# Nanocopter_V2_1.net
KiCad netlist of a schematic drawn in EAGLE
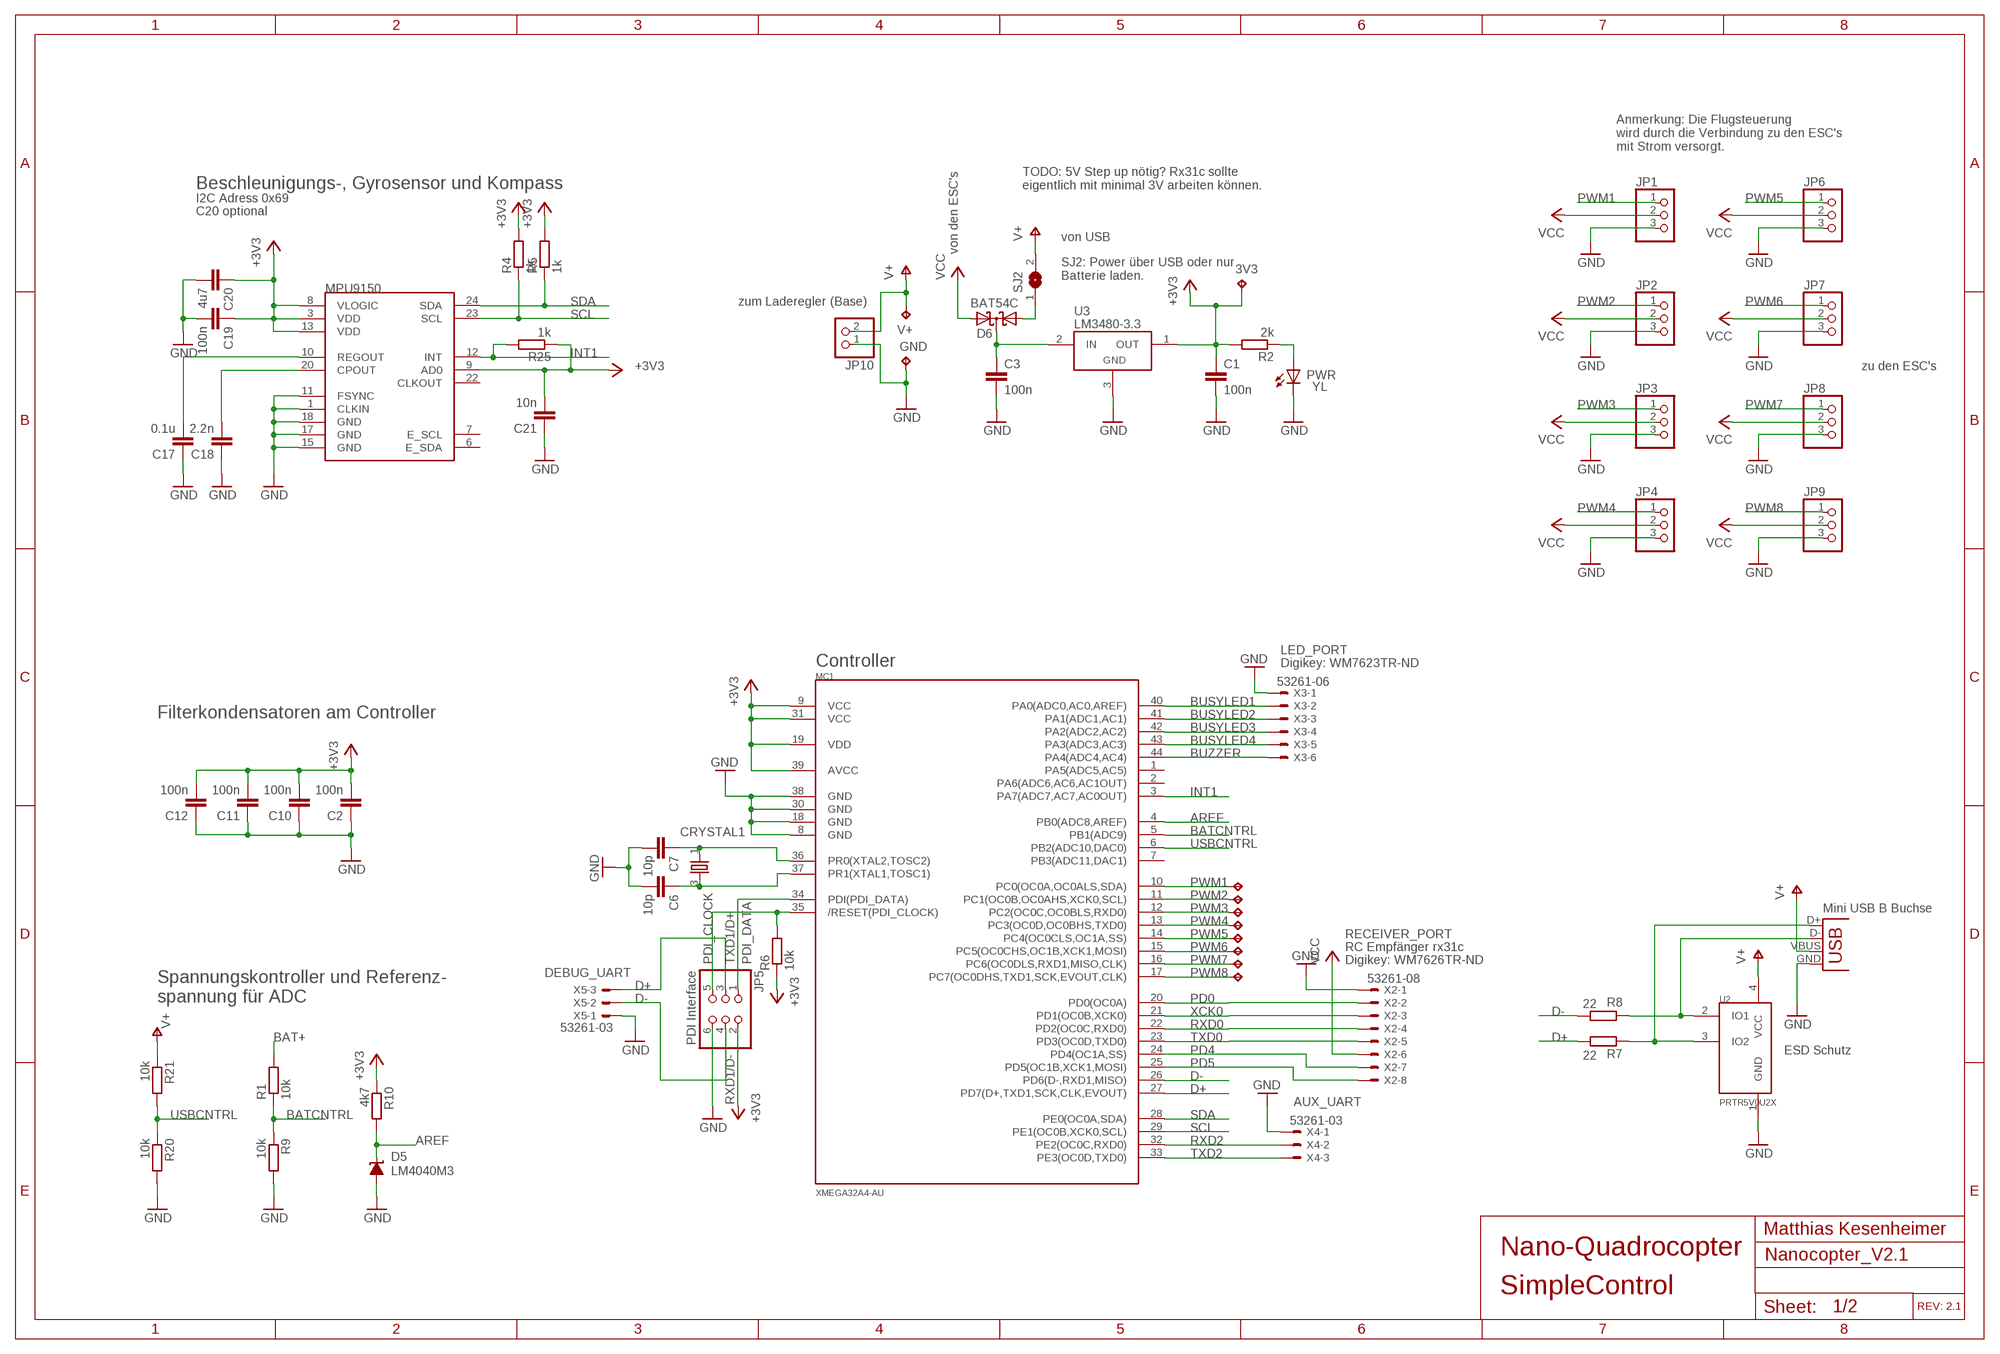
[diagram p0: schematic, sheet 1]
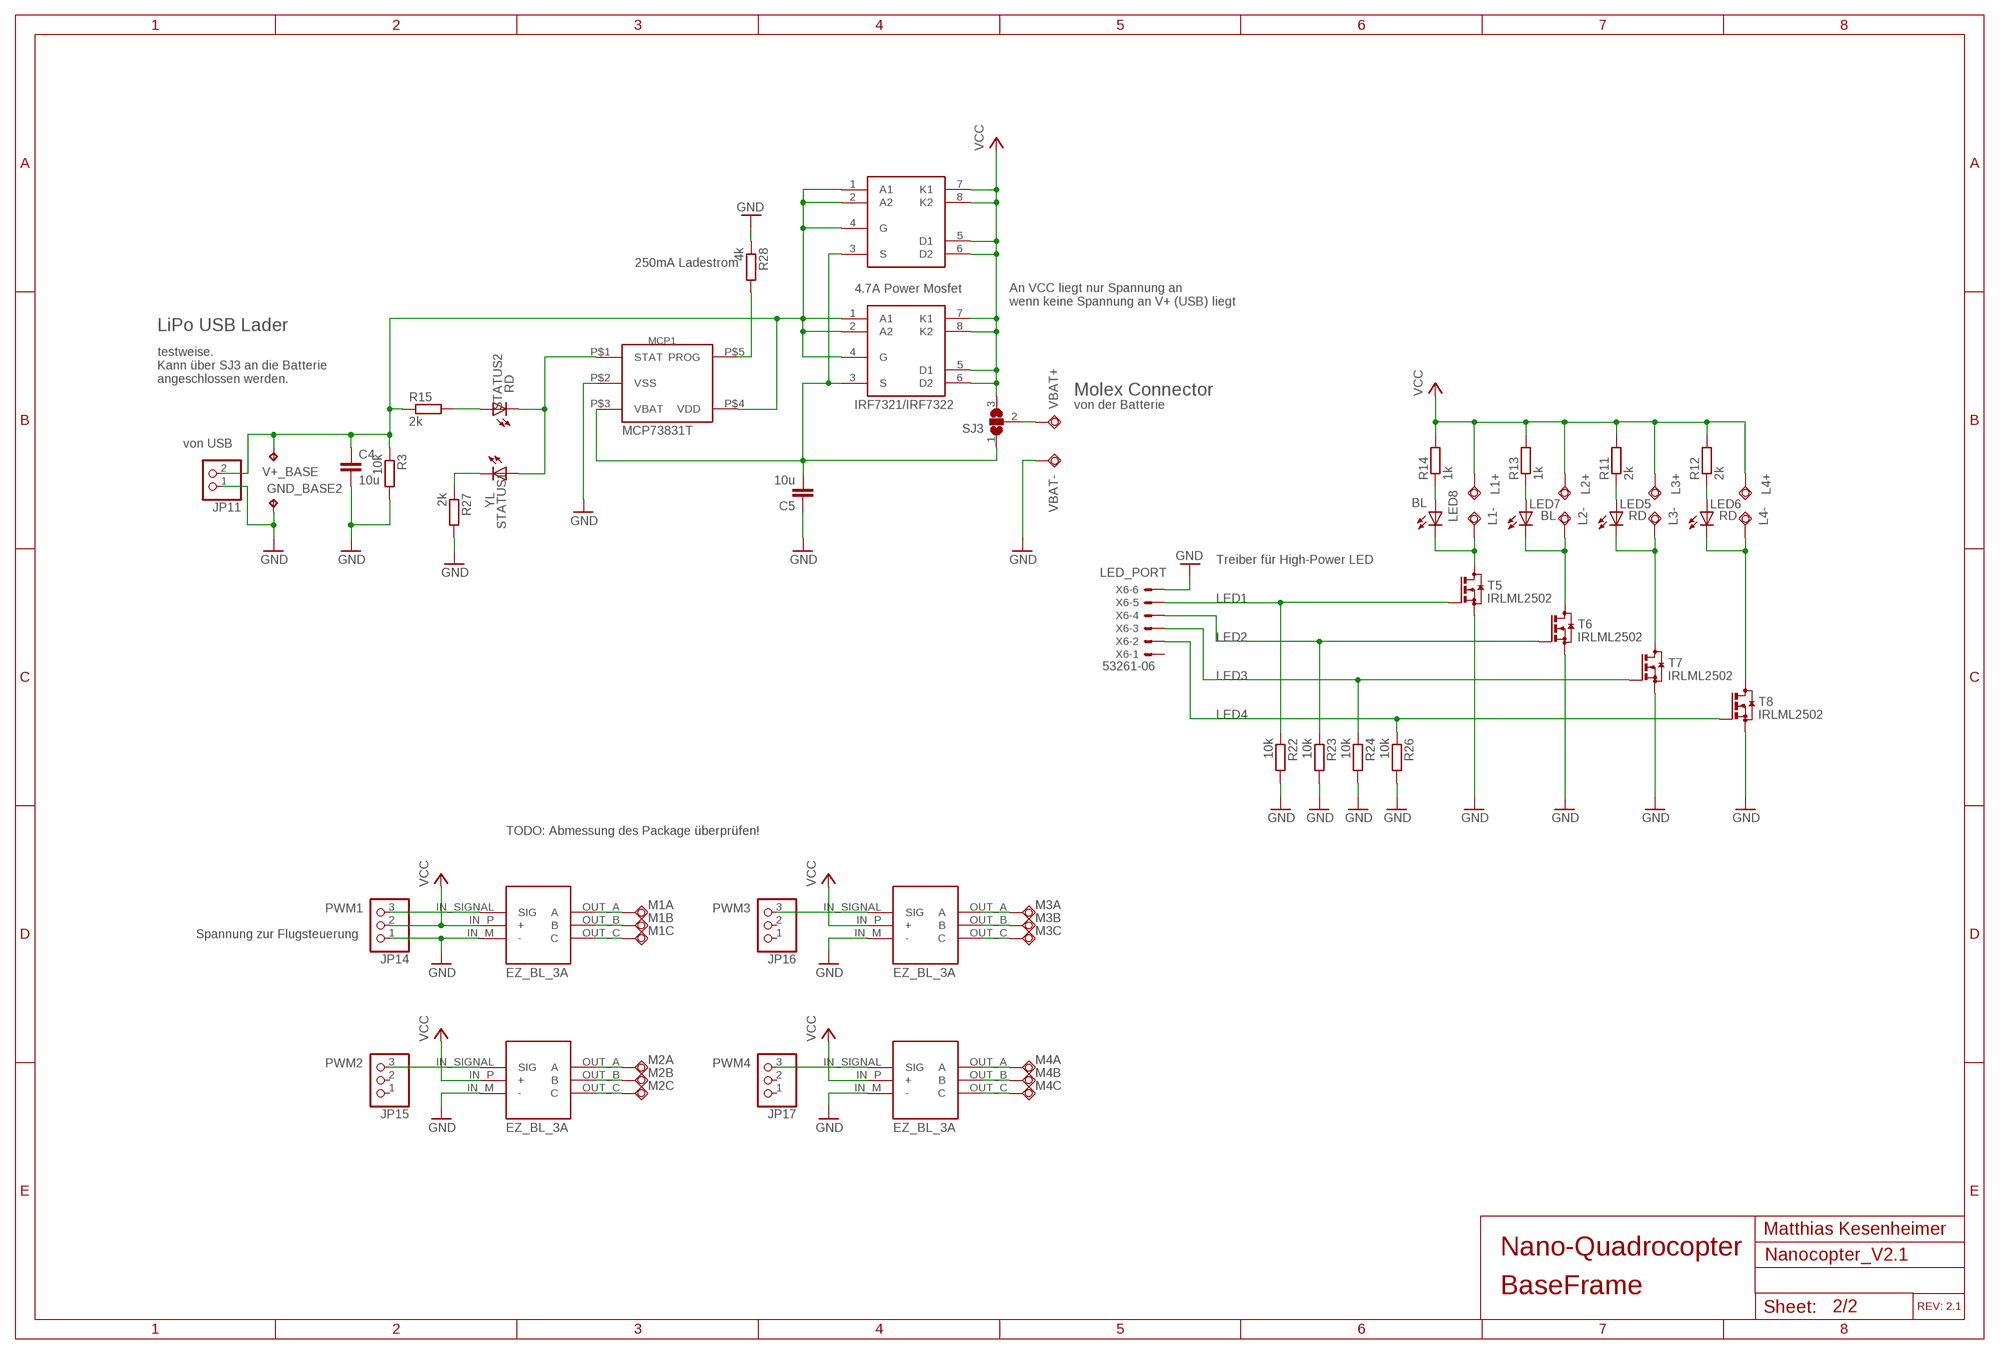
[diagram p1: schematic, sheet 2]

(export (version "E")
  (design (tool "Eeschema 10.0.6"))
  (components
    (comp (ref "C4")
      (value "10u")
      (footprint "eagle-import:C1206")
      (libsource (lib "eagle-import") (part "C-EUC1206"))
    )
    (comp (ref "C5")
      (value "10u")
      (footprint "eagle-import:C1206")
      (libsource (lib "eagle-import") (part "C-EUC1206"))
    )
    (comp (ref "GND_BASE2")
      (value "TPTP12SQ")
      (footprint "eagle-import:TP12SQ")
      (libsource (lib "eagle-import") (part "TPTP12SQ"))
    )
    (comp (ref "JP11")
      (value "PINHD-1X2/90")
      (footprint "eagle-import:1X02_90")
      (libsource (lib "eagle-import") (part "PINHD-1X2/90"))
    )
    (comp (ref "JP14")
      (value "PINHD-1X3/90")
      (footprint "eagle-import:1X03_90")
      (libsource (lib "eagle-import") (part "PINHD-1X3/90"))
    )
    (comp (ref "JP15")
      (value "PINHD-1X3/90")
      (footprint "eagle-import:1X03_90")
      (libsource (lib "eagle-import") (part "PINHD-1X3/90"))
    )
    (comp (ref "JP16")
      (value "PINHD-1X3/90")
      (footprint "eagle-import:1X03_90")
      (libsource (lib "eagle-import") (part "PINHD-1X3/90"))
    )
    (comp (ref "JP17")
      (value "PINHD-1X3/90")
      (footprint "eagle-import:1X03_90")
      (libsource (lib "eagle-import") (part "PINHD-1X3/90"))
    )
    (comp (ref "L1+")
      (value "TPSQTP20SQ")
      (footprint "eagle-import:TP20SQ")
      (libsource (lib "eagle-import") (part "TPSQTP20SQ"))
    )
    (comp (ref "L1-")
      (value "TPSQTP20SQ")
      (footprint "eagle-import:TP20SQ")
      (libsource (lib "eagle-import") (part "TPSQTP20SQ"))
    )
    (comp (ref "L2+")
      (value "TPSQTP20SQ")
      (footprint "eagle-import:TP20SQ")
      (libsource (lib "eagle-import") (part "TPSQTP20SQ"))
    )
    (comp (ref "L2-")
      (value "TPSQTP20SQ")
      (footprint "eagle-import:TP20SQ")
      (libsource (lib "eagle-import") (part "TPSQTP20SQ"))
    )
    (comp (ref "L3+")
      (value "TPSQTP20SQ")
      (footprint "eagle-import:TP20SQ")
      (libsource (lib "eagle-import") (part "TPSQTP20SQ"))
    )
    (comp (ref "L3-")
      (value "TPSQTP20SQ")
      (footprint "eagle-import:TP20SQ")
      (libsource (lib "eagle-import") (part "TPSQTP20SQ"))
    )
    (comp (ref "L4+")
      (value "TPSQTP20SQ")
      (footprint "eagle-import:TP20SQ")
      (libsource (lib "eagle-import") (part "TPSQTP20SQ"))
    )
    (comp (ref "L4-")
      (value "TPSQTP20SQ")
      (footprint "eagle-import:TP20SQ")
      (libsource (lib "eagle-import") (part "TPSQTP20SQ"))
    )
    (comp (ref "LED5")
      (value "RD")
      (footprint "eagle-import:CHIPLED_0603")
      (libsource (lib "eagle-import") (part "LEDCHIPLED_0603"))
    )
    (comp (ref "LED6")
      (value "RD")
      (footprint "eagle-import:CHIPLED_0603")
      (libsource (lib "eagle-import") (part "LEDCHIPLED_0603"))
    )
    (comp (ref "LED7")
      (value "BL")
      (footprint "eagle-import:CHIPLED_0603")
      (libsource (lib "eagle-import") (part "LEDCHIPLED_0603"))
    )
    (comp (ref "LED8")
      (value "BL")
      (footprint "eagle-import:CHIPLED_0603")
      (libsource (lib "eagle-import") (part "LEDCHIPLED_0603"))
    )
    (comp (ref "M1A")
      (value "TPSQTP20SQ")
      (footprint "eagle-import:TP20SQ")
      (libsource (lib "eagle-import") (part "TPSQTP20SQ"))
    )
    (comp (ref "M1B")
      (value "TPSQTP20SQ")
      (footprint "eagle-import:TP20SQ")
      (libsource (lib "eagle-import") (part "TPSQTP20SQ"))
    )
    (comp (ref "M1C")
      (value "TPSQTP20SQ")
      (footprint "eagle-import:TP20SQ")
      (libsource (lib "eagle-import") (part "TPSQTP20SQ"))
    )
    (comp (ref "M2A")
      (value "TPSQTP20SQ")
      (footprint "eagle-import:TP20SQ")
      (libsource (lib "eagle-import") (part "TPSQTP20SQ"))
    )
    (comp (ref "M2B")
      (value "TPSQTP20SQ")
      (footprint "eagle-import:TP20SQ")
      (libsource (lib "eagle-import") (part "TPSQTP20SQ"))
    )
    (comp (ref "M2C")
      (value "TPSQTP20SQ")
      (footprint "eagle-import:TP20SQ")
      (libsource (lib "eagle-import") (part "TPSQTP20SQ"))
    )
    (comp (ref "M3A")
      (value "TPSQTP20SQ")
      (footprint "eagle-import:TP20SQ")
      (libsource (lib "eagle-import") (part "TPSQTP20SQ"))
    )
    (comp (ref "M3B")
      (value "TPSQTP20SQ")
      (footprint "eagle-import:TP20SQ")
      (libsource (lib "eagle-import") (part "TPSQTP20SQ"))
    )
    (comp (ref "M3C")
      (value "TPSQTP20SQ")
      (footprint "eagle-import:TP20SQ")
      (libsource (lib "eagle-import") (part "TPSQTP20SQ"))
    )
    (comp (ref "M4A")
      (value "TPSQTP20SQ")
      (footprint "eagle-import:TP20SQ")
      (libsource (lib "eagle-import") (part "TPSQTP20SQ"))
    )
    (comp (ref "M4B")
      (value "TPSQTP20SQ")
      (footprint "eagle-import:TP20SQ")
      (libsource (lib "eagle-import") (part "TPSQTP20SQ"))
    )
    (comp (ref "M4C")
      (value "TPSQTP20SQ")
      (footprint "eagle-import:TP20SQ")
      (libsource (lib "eagle-import") (part "TPSQTP20SQ"))
    )
    (comp (ref "MCP1")
      (value "MCP73831")
      (footprint "eagle-import:5PIN_SOT23")
      (libsource (lib "eagle-import") (part "MCP73831"))
    )
    (comp (ref "R3")
      (value "10k")
      (footprint "eagle-import:R0603")
      (libsource (lib "eagle-import") (part "R-EU_R0603"))
    )
    (comp (ref "R11")
      (value "2k")
      (footprint "eagle-import:R0603")
      (libsource (lib "eagle-import") (part "R-EU_R0603"))
    )
    (comp (ref "R12")
      (value "2k")
      (footprint "eagle-import:R0603")
      (libsource (lib "eagle-import") (part "R-EU_R0603"))
    )
    (comp (ref "R13")
      (value "1k")
      (footprint "eagle-import:R0603")
      (libsource (lib "eagle-import") (part "R-EU_R0603"))
    )
    (comp (ref "R14")
      (value "1k")
      (footprint "eagle-import:R0603")
      (libsource (lib "eagle-import") (part "R-EU_R0603"))
    )
    (comp (ref "R15")
      (value "2k")
      (footprint "eagle-import:R0603")
      (libsource (lib "eagle-import") (part "R-EU_R0603"))
    )
    (comp (ref "R22")
      (value "10k")
      (footprint "eagle-import:R0603")
      (libsource (lib "eagle-import") (part "R-EU_R0603"))
    )
    (comp (ref "R23")
      (value "10k")
      (footprint "eagle-import:R0603")
      (libsource (lib "eagle-import") (part "R-EU_R0603"))
    )
    (comp (ref "R24")
      (value "10k")
      (footprint "eagle-import:R0603")
      (libsource (lib "eagle-import") (part "R-EU_R0603"))
    )
    (comp (ref "R26")
      (value "10k")
      (footprint "eagle-import:R0603")
      (libsource (lib "eagle-import") (part "R-EU_R0603"))
    )
    (comp (ref "R27")
      (value "2k")
      (footprint "eagle-import:R0603")
      (libsource (lib "eagle-import") (part "R-EU_R0603"))
    )
    (comp (ref "R28")
      (value "4k")
      (footprint "eagle-import:R0603")
      (libsource (lib "eagle-import") (part "R-EU_R0603"))
    )
    (comp (ref "SJ3")
      (value "SJ2W")
      (footprint "eagle-import:SJ_2")
      (libsource (lib "eagle-import") (part "SJ2W"))
    )
    (comp (ref "STATUS1")
      (value "YL")
      (footprint "eagle-import:CHIPLED_0603")
      (libsource (lib "eagle-import") (part "LEDCHIPLED_0603"))
    )
    (comp (ref "STATUS2")
      (value "RD")
      (footprint "eagle-import:CHIPLED_0603")
      (libsource (lib "eagle-import") (part "LEDCHIPLED_0603"))
    )
    (comp (ref "T5")
      (value "IRLML2502")
      (footprint "eagle-import:SOT23")
      (libsource (lib "eagle-import") (part "BSS123"))
    )
    (comp (ref "T6")
      (value "IRLML2502")
      (footprint "eagle-import:SOT23")
      (libsource (lib "eagle-import") (part "BSS123"))
    )
    (comp (ref "T7")
      (value "IRLML2502")
      (footprint "eagle-import:SOT23")
      (libsource (lib "eagle-import") (part "BSS123"))
    )
    (comp (ref "T8")
      (value "IRLML2502")
      (footprint "eagle-import:SOT23")
      (libsource (lib "eagle-import") (part "BSS123"))
    )
    (comp (ref "U$1")
      (value "EAZY_BL_3A")
      (footprint "eagle-import:EZ_BL_3A_P")
      (libsource (lib "eagle-import") (part "EAZY_BL_3A"))
    )
    (comp (ref "U$2")
      (value "EAZY_BL_3A")
      (footprint "eagle-import:EZ_BL_3A_P")
      (libsource (lib "eagle-import") (part "EAZY_BL_3A"))
    )
    (comp (ref "U$3")
      (value "EAZY_BL_3A")
      (footprint "eagle-import:EZ_BL_3A_P")
      (libsource (lib "eagle-import") (part "EAZY_BL_3A"))
    )
    (comp (ref "U$4")
      (value "EAZY_BL_3A")
      (footprint "eagle-import:EZ_BL_3A_P")
      (libsource (lib "eagle-import") (part "EAZY_BL_3A"))
    )
    (comp (ref "U$5")
      (value "IRF7321")
      (footprint "eagle-import:SO8")
      (libsource (lib "eagle-import") (part "IRF7321"))
    )
    (comp (ref "U$6")
      (value "IRF7321")
      (footprint "eagle-import:SO8")
      (libsource (lib "eagle-import") (part "IRF7321"))
    )
    (comp (ref "V+_BASE")
      (value "TPTP12SQ")
      (footprint "eagle-import:TP12SQ")
      (libsource (lib "eagle-import") (part "TPTP12SQ"))
    )
    (comp (ref "VBAT+")
      (value "TPSQTP20SQ")
      (footprint "eagle-import:TP20SQ")
      (libsource (lib "eagle-import") (part "TPSQTP20SQ"))
    )
    (comp (ref "VBAT-")
      (value "TPSQTP20SQ")
      (footprint "eagle-import:TP20SQ")
      (libsource (lib "eagle-import") (part "TPSQTP20SQ"))
    )
    (comp (ref "X6")
      (value "53261-06")
      (footprint "eagle-import:53261-06")
      (libsource (lib "eagle-import") (part "53?-06261"))
    )
    (comp (ref "3V1")
      (value "TPTP12SQ")
      (footprint "eagle-import:TP12SQ")
      (libsource (lib "eagle-import") (part "TPTP12SQ"))
    )
    (comp (ref "3V2")
      (value "TPTP12SQ")
      (footprint "eagle-import:TP12SQ")
      (libsource (lib "eagle-import") (part "TPTP12SQ"))
    )
    (comp (ref "3V3")
      (value "TPTP12SQ")
      (footprint "eagle-import:TP12SQ")
      (libsource (lib "eagle-import") (part "TPTP12SQ"))
    )
    (comp (ref "3V4")
      (value "TPTP12SQ")
      (footprint "eagle-import:TP12SQ")
      (libsource (lib "eagle-import") (part "TPTP12SQ"))
    )
    (comp (ref "3V5")
      (value "TPTP12SQ")
      (footprint "eagle-import:TP12SQ")
      (libsource (lib "eagle-import") (part "TPTP12SQ"))
    )
    (comp (ref "3V6")
      (value "TPTP12SQ")
      (footprint "eagle-import:TP12SQ")
      (libsource (lib "eagle-import") (part "TPTP12SQ"))
    )
    (comp (ref "3V7")
      (value "TPTP12SQ")
      (footprint "eagle-import:TP12SQ")
      (libsource (lib "eagle-import") (part "TPTP12SQ"))
    )
    (comp (ref "3V8")
      (value "TPTP12SQ")
      (footprint "eagle-import:TP12SQ")
      (libsource (lib "eagle-import") (part "TPTP12SQ"))
    )
    (comp (ref "C1")
      (value "100n")
      (footprint "eagle-import:C0603")
      (libsource (lib "eagle-import") (part "C-EUC0603"))
    )
    (comp (ref "C2")
      (value "100n")
      (footprint "eagle-import:C0603")
      (libsource (lib "eagle-import") (part "C-EUC0603"))
    )
    (comp (ref "C3")
      (value "100n")
      (footprint "eagle-import:C0603")
      (libsource (lib "eagle-import") (part "C-EUC0603"))
    )
    (comp (ref "C6")
      (value "10p")
      (footprint "eagle-import:C0603")
      (libsource (lib "eagle-import") (part "C-EUC0603"))
    )
    (comp (ref "C7")
      (value "10p")
      (footprint "eagle-import:C0603")
      (libsource (lib "eagle-import") (part "C-EUC0603"))
    )
    (comp (ref "C10")
      (value "100n")
      (footprint "eagle-import:C0603")
      (libsource (lib "eagle-import") (part "C-EUC0603"))
    )
    (comp (ref "C11")
      (value "100n")
      (footprint "eagle-import:C0603")
      (libsource (lib "eagle-import") (part "C-EUC0603"))
    )
    (comp (ref "C12")
      (value "100n")
      (footprint "eagle-import:C0603")
      (libsource (lib "eagle-import") (part "C-EUC0603"))
    )
    (comp (ref "C17")
      (value "0.1u")
      (footprint "eagle-import:C0603")
      (libsource (lib "eagle-import") (part "C-EUC0603"))
    )
    (comp (ref "C18")
      (value "2.2n")
      (footprint "eagle-import:C0603")
      (libsource (lib "eagle-import") (part "C-EUC0603"))
    )
    (comp (ref "C19")
      (value "100n")
      (footprint "eagle-import:C0603")
      (libsource (lib "eagle-import") (part "C-EUC0603"))
    )
    (comp (ref "C20")
      (value "4u7")
      (footprint "eagle-import:C0603")
      (libsource (lib "eagle-import") (part "C-EUC0603"))
    )
    (comp (ref "C21")
      (value "10n")
      (footprint "eagle-import:C0603")
      (libsource (lib "eagle-import") (part "C-EUC0603"))
    )
    (comp (ref "CRYSTAL1")
      (value "CRYSTAL4PIN")
      (footprint "eagle-import:CRYSTAL-4PIN")
      (libsource (lib "eagle-import") (part "CRYSTAL4PIN"))
    )
    (comp (ref "D5")
      (value "LM4040M3")
      (footprint "eagle-import:SOT-23")
      (libsource (lib "eagle-import") (part "LM4040M3"))
    )
    (comp (ref "D6")
      (value "BAT54C")
      (footprint "eagle-import:SOT23")
      (libsource (lib "eagle-import") (part "BAT54C"))
    )
    (comp (ref "GND")
      (value "TPTP12SQ")
      (footprint "eagle-import:TP12SQ")
      (libsource (lib "eagle-import") (part "TPTP12SQ"))
    )
    (comp (ref "JP1")
      (value "PINHD-1X3")
      (footprint "eagle-import:1X03")
      (libsource (lib "eagle-import") (part "PINHD-1X3"))
    )
    (comp (ref "JP2")
      (value "PINHD-1X3")
      (footprint "eagle-import:1X03")
      (libsource (lib "eagle-import") (part "PINHD-1X3"))
    )
    (comp (ref "JP3")
      (value "PINHD-1X3")
      (footprint "eagle-import:1X03")
      (libsource (lib "eagle-import") (part "PINHD-1X3"))
    )
    (comp (ref "JP4")
      (value "PINHD-1X3")
      (footprint "eagle-import:1X03")
      (libsource (lib "eagle-import") (part "PINHD-1X3"))
    )
    (comp (ref "JP5")
      (value "PDI Interface")
      (footprint "eagle-import:2X03")
      (libsource (lib "eagle-import") (part "PINHD-2X3"))
    )
    (comp (ref "JP6")
      (value "PINHD-1X3")
      (footprint "eagle-import:1X03")
      (libsource (lib "eagle-import") (part "PINHD-1X3"))
    )
    (comp (ref "JP7")
      (value "PINHD-1X3")
      (footprint "eagle-import:1X03")
      (libsource (lib "eagle-import") (part "PINHD-1X3"))
    )
    (comp (ref "JP8")
      (value "PINHD-1X3")
      (footprint "eagle-import:1X03")
      (libsource (lib "eagle-import") (part "PINHD-1X3"))
    )
    (comp (ref "JP9")
      (value "PINHD-1X3")
      (footprint "eagle-import:1X03")
      (libsource (lib "eagle-import") (part "PINHD-1X3"))
    )
    (comp (ref "JP10")
      (value "PINHD-1X2")
      (footprint "eagle-import:1X02")
      (libsource (lib "eagle-import") (part "PINHD-1X2"))
    )
    (comp (ref "MC1")
      (value "XMEGA32A4-AU")
      (footprint "eagle-import:TQFP44")
      (libsource (lib "eagle-import") (part "XMEGA32A4-AU"))
    )
    (comp (ref "MPU9150")
      (value "MPU-9150QFN-24-NP")
      (footprint "eagle-import:QFN-24-NP")
      (libsource (lib "eagle-import") (part "MPU-9150QFN-24-NP"))
    )
    (comp (ref "PWM1")
      (value "TPTP12SQ")
      (footprint "eagle-import:TP12SQ")
      (libsource (lib "eagle-import") (part "TPTP12SQ"))
    )
    (comp (ref "PWR")
      (value "YL")
      (footprint "eagle-import:CHIPLED_0603")
      (libsource (lib "eagle-import") (part "LEDCHIPLED_0603"))
    )
    (comp (ref "R1")
      (value "10k")
      (footprint "eagle-import:R0603")
      (libsource (lib "eagle-import") (part "R-EU_R0603"))
    )
    (comp (ref "R2")
      (value "2k")
      (footprint "eagle-import:R0603")
      (libsource (lib "eagle-import") (part "R-EU_R0603"))
    )
    (comp (ref "R4")
      (value "1k")
      (footprint "eagle-import:R0603")
      (libsource (lib "eagle-import") (part "R-EU_R0603"))
    )
    (comp (ref "R5")
      (value "1k")
      (footprint "eagle-import:R0603")
      (libsource (lib "eagle-import") (part "R-EU_R0603"))
    )
    (comp (ref "R6")
      (value "10k")
      (footprint "eagle-import:R0603")
      (libsource (lib "eagle-import") (part "R-EU_R0603"))
    )
    (comp (ref "R7")
      (value "22")
      (footprint "eagle-import:R0603")
      (libsource (lib "eagle-import") (part "R-EU_R0603"))
    )
    (comp (ref "R8")
      (value "22")
      (footprint "eagle-import:R0603")
      (libsource (lib "eagle-import") (part "R-EU_R0603"))
    )
    (comp (ref "R9")
      (value "10k")
      (footprint "eagle-import:R0603")
      (libsource (lib "eagle-import") (part "R-EU_R0603"))
    )
    (comp (ref "R10")
      (value "4k7")
      (footprint "eagle-import:R0603")
      (libsource (lib "eagle-import") (part "R-EU_R0603"))
    )
    (comp (ref "R20")
      (value "10k")
      (footprint "eagle-import:R0603")
      (libsource (lib "eagle-import") (part "R-EU_R0603"))
    )
    (comp (ref "R21")
      (value "10k")
      (footprint "eagle-import:R0603")
      (libsource (lib "eagle-import") (part "R-EU_R0603"))
    )
    (comp (ref "R25")
      (value "1k")
      (footprint "eagle-import:R0603")
      (libsource (lib "eagle-import") (part "R-EU_R0603"))
    )
    (comp (ref "SJ2") (value "SJ") (footprint "eagle-import:SJ") (libsource (lib "eagle-import") (part "SJ")))
    (comp (ref "U2")
      (value "PRTR5V0U2X")
      (footprint "eagle-import:SOT143B")
      (libsource (lib "eagle-import") (part "PRTR5V0U2X"))
    )
    (comp (ref "U3")
      (value "LM3480-3.3")
      (footprint "eagle-import:SOT-23-3")
      (libsource (lib "eagle-import") (part "LM3480-3.3"))
    )
    (comp (ref "V+")
      (value "TPTP12SQ")
      (footprint "eagle-import:TP12SQ")
      (libsource (lib "eagle-import") (part "TPTP12SQ"))
    )
    (comp (ref "X1")
      (value "USBSMD")
      (footprint "eagle-import:USB-MINIB")
      (libsource (lib "eagle-import") (part "USBSMD"))
    )
    (comp (ref "X2")
      (value "53261-08")
      (footprint "eagle-import:53261-08")
      (libsource (lib "eagle-import") (part "53?-08261"))
    )
    (comp (ref "X3")
      (value "53261-06")
      (footprint "eagle-import:53261-06")
      (libsource (lib "eagle-import") (part "53?-06261"))
    )
    (comp (ref "X4")
      (value "53261-03")
      (footprint "eagle-import:53261-03")
      (fields (field (name "MF") "MOLEX") (field (name "MPN") "53261-0390"))
      (libsource (lib "eagle-import") (part "53?-03261"))
    )
    (comp (ref "X5")
      (value "53261-03")
      (footprint "eagle-import:53261-03")
      (fields (field (name "MF") "MOLEX") (field (name "MPN") "53261-0390"))
      (libsource (lib "eagle-import") (part "53?-03261"))
    )
  )
  (nets
    (net (code "1") (name "+3V3") (class "Default")
      (node (ref "3V3") (pin "TP") (pinfunction "TP_TP") (pintype "input"))
      (node (ref "C1") (pin "1") (pinfunction "1_1") (pintype "passive"))
      (node (ref "C10") (pin "2") (pinfunction "2_2") (pintype "passive"))
      (node (ref "C11") (pin "2") (pinfunction "2_2") (pintype "passive"))
      (node (ref "C12") (pin "2") (pinfunction "2_2") (pintype "passive"))
      (node (ref "C19") (pin "1") (pinfunction "1_1") (pintype "passive"))
      (node (ref "C2") (pin "2") (pinfunction "2_2") (pintype "passive"))
      (node (ref "C20") (pin "1") (pinfunction "1_1") (pintype "passive"))
      (node (ref "C21") (pin "2") (pinfunction "2_2") (pintype "passive"))
      (node (ref "JP5") (pin "2") (pinfunction "2_2") (pintype "passive"))
      (node (ref "MC1") (pin "19") (pinfunction "VDD_19") (pintype "power_in"))
      (node (ref "MC1") (pin "31") (pinfunction "VCC_31") (pintype "power_in"))
      (node (ref "MC1") (pin "39") (pinfunction "AVCC_39") (pintype "power_in"))
      (node (ref "MC1") (pin "9") (pinfunction "VCC_9") (pintype "power_in"))
      (node (ref "MPU9150") (pin "13") (pinfunction "VDD_13") (pintype "bidirectional"))
      (node (ref "MPU9150") (pin "3") (pinfunction "VDD_3") (pintype "bidirectional"))
      (node (ref "MPU9150") (pin "8") (pinfunction "VLOGIC_8") (pintype "bidirectional"))
      (node (ref "MPU9150") (pin "9") (pinfunction "AD0_9") (pintype "bidirectional"))
      (node (ref "R10") (pin "1") (pinfunction "1_1") (pintype "passive"))
      (node (ref "R2") (pin "2") (pinfunction "2_2") (pintype "passive"))
      (node (ref "R25") (pin "1") (pinfunction "1_1") (pintype "passive"))
      (node (ref "R4") (pin "2") (pinfunction "2_2") (pintype "passive"))
      (node (ref "R5") (pin "2") (pinfunction "2_2") (pintype "passive"))
      (node (ref "R6") (pin "1") (pinfunction "1_1") (pintype "passive"))
      (node (ref "U3") (pin "1") (pinfunction "OUT_1") (pintype "power_in"))
    )
    (net (code "2") (name "AREF") (class "Default")
      (node (ref "D5") (pin "1") (pinfunction "C_1") (pintype "passive"))
      (node (ref "MC1") (pin "4") (pinfunction "PB0(ADC8,AREF)_4") (pintype "bidirectional"))
      (node (ref "R10") (pin "2") (pinfunction "2_2") (pintype "passive"))
    )
    (net (code "3") (name "BAT+") (class "Default")
      (node (ref "R1") (pin "2") (pinfunction "2_2") (pintype "passive"))
    )
    (net (code "4") (name "BATCNTRL") (class "Default")
      (node (ref "MC1") (pin "5") (pinfunction "PB1(ADC9)_5") (pintype "bidirectional"))
      (node (ref "R1") (pin "1") (pinfunction "1_1") (pintype "passive"))
      (node (ref "R9") (pin "1") (pinfunction "1_1") (pintype "passive"))
    )
    (net (code "5") (name "BUSYLED1") (class "Default")
      (node (ref "MC1") (pin "40") (pinfunction "PA0(ADC0,AC0,AREF)_40") (pintype "bidirectional"))
      (node (ref "X3") (pin "2") (pinfunction "S_2") (pintype "passive"))
    )
    (net (code "6") (name "BUSYLED2") (class "Default")
      (node (ref "MC1") (pin "41") (pinfunction "PA1(ADC1,AC1)_41") (pintype "bidirectional"))
      (node (ref "X3") (pin "3") (pinfunction "S_3") (pintype "passive"))
    )
    (net (code "7") (name "BUSYLED3") (class "Default")
      (node (ref "MC1") (pin "42") (pinfunction "PA2(ADC2,AC2)_42") (pintype "bidirectional"))
      (node (ref "X3") (pin "4") (pinfunction "S_4") (pintype "passive"))
    )
    (net (code "8") (name "BUSYLED4") (class "Default")
      (node (ref "MC1") (pin "43") (pinfunction "PA3(ADC3,AC3)_43") (pintype "bidirectional"))
      (node (ref "X3") (pin "5") (pinfunction "S_5") (pintype "passive"))
    )
    (net (code "9") (name "BUZZER") (class "Default")
      (node (ref "MC1") (pin "44") (pinfunction "PA4(ADC4,AC4)_44") (pintype "bidirectional"))
      (node (ref "X3") (pin "6") (pinfunction "S_6") (pintype "passive"))
    )
    (net (code "10") (name "D+") (class "Default")
      (node (ref "JP5") (pin "3") (pinfunction "3_3") (pintype "passive"))
      (node (ref "MC1") (pin "27") (pinfunction "PD7(D+,TXD1,SCK,CLK,EVOUT)_27") (pintype "bidirectional"))
      (node (ref "R7") (pin "2") (pinfunction "2_2") (pintype "passive"))
      (node (ref "X5") (pin "3") (pinfunction "S_3") (pintype "passive"))
    )
    (net (code "11") (name "D-") (class "Default")
      (node (ref "JP5") (pin "4") (pinfunction "4_4") (pintype "passive"))
      (node (ref "MC1") (pin "26") (pinfunction "PD6(D-,RXD1,MISO)_26") (pintype "bidirectional"))
      (node (ref "R8") (pin "2") (pinfunction "2_2") (pintype "passive"))
      (node (ref "X5") (pin "2") (pinfunction "S_2") (pintype "passive"))
    )
    (net (code "12") (name "GND") (class "Default")
      (node (ref "C1") (pin "2") (pinfunction "2_2") (pintype "passive"))
      (node (ref "C10") (pin "1") (pinfunction "1_1") (pintype "passive"))
      (node (ref "C11") (pin "1") (pinfunction "1_1") (pintype "passive"))
      (node (ref "C12") (pin "1") (pinfunction "1_1") (pintype "passive"))
      (node (ref "C17") (pin "1") (pinfunction "1_1") (pintype "passive"))
      (node (ref "C18") (pin "1") (pinfunction "1_1") (pintype "passive"))
      (node (ref "C19") (pin "2") (pinfunction "2_2") (pintype "passive"))
      (node (ref "C2") (pin "1") (pinfunction "1_1") (pintype "passive"))
      (node (ref "C20") (pin "2") (pinfunction "2_2") (pintype "passive"))
      (node (ref "C21") (pin "1") (pinfunction "1_1") (pintype "passive"))
      (node (ref "C3") (pin "2") (pinfunction "2_2") (pintype "passive"))
      (node (ref "C4") (pin "2") (pinfunction "2_2") (pintype "passive"))
      (node (ref "C5") (pin "1") (pinfunction "1_1") (pintype "passive"))
      (node (ref "C6") (pin "2") (pinfunction "2_2") (pintype "passive"))
      (node (ref "C7") (pin "2") (pinfunction "2_2") (pintype "passive"))
      (node (ref "D5") (pin "2") (pinfunction "A_2") (pintype "passive"))
      (node (ref "GND") (pin "TP") (pinfunction "TP_TP") (pintype "input"))
      (node (ref "GND_BASE2") (pin "TP") (pinfunction "TP_TP") (pintype "input"))
      (node (ref "JP1") (pin "3") (pinfunction "3_3") (pintype "passive"))
      (node (ref "JP10") (pin "1") (pinfunction "1_1") (pintype "passive"))
      (node (ref "JP11") (pin "1") (pinfunction "1_1") (pintype "passive"))
      (node (ref "JP14") (pin "1") (pinfunction "1_1") (pintype "passive"))
      (node (ref "JP2") (pin "3") (pinfunction "3_3") (pintype "passive"))
      (node (ref "JP3") (pin "3") (pinfunction "3_3") (pintype "passive"))
      (node (ref "JP4") (pin "3") (pinfunction "3_3") (pintype "passive"))
      (node (ref "JP5") (pin "6") (pinfunction "6_6") (pintype "passive"))
      (node (ref "JP6") (pin "3") (pinfunction "3_3") (pintype "passive"))
      (node (ref "JP7") (pin "3") (pinfunction "3_3") (pintype "passive"))
      (node (ref "JP8") (pin "3") (pinfunction "3_3") (pintype "passive"))
      (node (ref "JP9") (pin "3") (pinfunction "3_3") (pintype "passive"))
      (node (ref "MC1") (pin "18") (pinfunction "GND_18") (pintype "power_in"))
      (node (ref "MC1") (pin "30") (pinfunction "GND_30") (pintype "power_in"))
      (node (ref "MC1") (pin "38") (pinfunction "GND_38") (pintype "power_in"))
      (node (ref "MC1") (pin "8") (pinfunction "GND_8") (pintype "power_in"))
      (node (ref "MCP1") (pin "P$2") (pinfunction "VSS_P$2") (pintype "bidirectional"))
      (node (ref "MPU9150") (pin "1") (pinfunction "CLKIN_1") (pintype "bidirectional"))
      (node (ref "MPU9150") (pin "11") (pinfunction "FSYNC_11") (pintype "bidirectional"))
      (node (ref "MPU9150") (pin "15") (pinfunction "GND_15") (pintype "bidirectional"))
      (node (ref "MPU9150") (pin "17") (pinfunction "GND_17") (pintype "bidirectional"))
      (node (ref "MPU9150") (pin "18") (pinfunction "GND_18") (pintype "bidirectional"))
      (node (ref "PWR") (pin "C") (pinfunction "C_C") (pintype "passive"))
      (node (ref "R20") (pin "2") (pinfunction "2_2") (pintype "passive"))
      (node (ref "R22") (pin "2") (pinfunction "2_2") (pintype "passive"))
      (node (ref "R23") (pin "2") (pinfunction "2_2") (pintype "passive"))
      (node (ref "R24") (pin "2") (pinfunction "2_2") (pintype "passive"))
      (node (ref "R26") (pin "2") (pinfunction "2_2") (pintype "passive"))
      (node (ref "R27") (pin "2") (pinfunction "2_2") (pintype "passive"))
      (node (ref "R28") (pin "1") (pinfunction "1_1") (pintype "passive"))
      (node (ref "R3") (pin "2") (pinfunction "2_2") (pintype "passive"))
      (node (ref "R9") (pin "2") (pinfunction "2_2") (pintype "passive"))
      (node (ref "T5") (pin "2") (pinfunction "S_2") (pintype "passive"))
      (node (ref "T6") (pin "2") (pinfunction "S_2") (pintype "passive"))
      (node (ref "T7") (pin "2") (pinfunction "S_2") (pintype "passive"))
      (node (ref "T8") (pin "2") (pinfunction "S_2") (pintype "passive"))
      (node (ref "U$1") (pin "IN_M") (pinfunction "-_IN_M") (pintype "bidirectional"))
      (node (ref "U$2") (pin "IN_M") (pinfunction "-_IN_M") (pintype "bidirectional"))
      (node (ref "U$3") (pin "IN_M") (pinfunction "-_IN_M") (pintype "bidirectional"))
      (node (ref "U$4") (pin "IN_M") (pinfunction "-_IN_M") (pintype "bidirectional"))
      (node (ref "U2") (pin "1") (pinfunction "GND_1") (pintype "power_in"))
      (node (ref "U3") (pin "3") (pinfunction "GND_3") (pintype "power_in"))
      (node (ref "VBAT-") (pin "TP") (pinfunction "TP_TP") (pintype "input"))
      (node (ref "X1") (pin "GND") (pinfunction "GND_GND") (pintype "bidirectional"))
      (node (ref "X2") (pin "1") (pinfunction "S_1") (pintype "passive"))
      (node (ref "X3") (pin "1") (pinfunction "S_1") (pintype "passive"))
      (node (ref "X4") (pin "1") (pinfunction "S_1") (pintype "passive"))
      (node (ref "X5") (pin "1") (pinfunction "S_1") (pintype "passive"))
      (node (ref "X6") (pin "6") (pinfunction "S_6") (pintype "passive"))
    )
    (net (code "13") (name "INT1") (class "Default")
      (node (ref "MC1") (pin "3") (pinfunction "PA7(ADC7,AC7,AC0OUT)_3") (pintype "bidirectional"))
      (node (ref "MPU9150") (pin "12") (pinfunction "INT_12") (pintype "bidirectional"))
      (node (ref "R25") (pin "2") (pinfunction "2_2") (pintype "passive"))
    )
    (net (code "14") (name "LED1") (class "Default")
      (node (ref "R22") (pin "1") (pinfunction "1_1") (pintype "passive"))
      (node (ref "T5") (pin "1") (pinfunction "G_1") (pintype "passive"))
      (node (ref "X6") (pin "5") (pinfunction "S_5") (pintype "passive"))
    )
    (net (code "15") (name "LED2") (class "Default")
      (node (ref "R23") (pin "1") (pinfunction "1_1") (pintype "passive"))
      (node (ref "T6") (pin "1") (pinfunction "G_1") (pintype "passive"))
      (node (ref "X6") (pin "4") (pinfunction "S_4") (pintype "passive"))
    )
    (net (code "16") (name "LED3") (class "Default")
      (node (ref "R24") (pin "1") (pinfunction "1_1") (pintype "passive"))
      (node (ref "T7") (pin "1") (pinfunction "G_1") (pintype "passive"))
      (node (ref "X6") (pin "3") (pinfunction "S_3") (pintype "passive"))
    )
    (net (code "17") (name "LED4") (class "Default")
      (node (ref "R26") (pin "1") (pinfunction "1_1") (pintype "passive"))
      (node (ref "T8") (pin "1") (pinfunction "G_1") (pintype "passive"))
      (node (ref "X6") (pin "2") (pinfunction "S_2") (pintype "passive"))
    )
    (net (code "18") (name "Net-(CRYSTAL1-2)") (class "Default")
      (node (ref "C6") (pin "1") (pinfunction "1_1") (pintype "passive"))
      (node (ref "CRYSTAL1") (pin "3") (pinfunction "2_3") (pintype "passive"))
      (node (ref "MC1") (pin "37") (pinfunction "PR1(XTAL1,TOSC1)_37") (pintype "bidirectional"))
    )
    (net (code "19") (name "Net-(D6-A1)") (class "Default")
      (node (ref "D6") (pin "1") (pinfunction "A1_1") (pintype "passive"))
      (node (ref "SJ2") (pin "1") (pinfunction "1_1") (pintype "passive"))
    )
    (net (code "20") (name "Net-(D6-CC)") (class "Default")
      (node (ref "C3") (pin "1") (pinfunction "1_1") (pintype "passive"))
      (node (ref "D6") (pin "3") (pinfunction "CC_3") (pintype "passive"))
      (node (ref "U3") (pin "2") (pinfunction "IN_2") (pintype "power_in"))
    )
    (net (code "21") (name "Net-(LED5-PadA)") (class "Default")
      (node (ref "LED5") (pin "A") (pinfunction "A_A") (pintype "passive"))
      (node (ref "R11") (pin "1") (pinfunction "1_1") (pintype "passive"))
    )
    (net (code "22") (name "Net-(LED6-PadA)") (class "Default")
      (node (ref "LED6") (pin "A") (pinfunction "A_A") (pintype "passive"))
      (node (ref "R12") (pin "1") (pinfunction "1_1") (pintype "passive"))
    )
    (net (code "23") (name "Net-(LED7-PadA)") (class "Default")
      (node (ref "LED7") (pin "A") (pinfunction "A_A") (pintype "passive"))
      (node (ref "R13") (pin "1") (pinfunction "1_1") (pintype "passive"))
    )
    (net (code "24") (name "Net-(LED8-PadA)") (class "Default")
      (node (ref "LED8") (pin "A") (pinfunction "A_A") (pintype "passive"))
      (node (ref "R14") (pin "1") (pinfunction "1_1") (pintype "passive"))
    )
    (net (code "25") (name "Net-(MC1-PR0(XTAL2,TOSC2))") (class "Default")
      (node (ref "C7") (pin "1") (pinfunction "1_1") (pintype "passive"))
      (node (ref "CRYSTAL1") (pin "1") (pinfunction "1_1") (pintype "passive"))
      (node (ref "MC1") (pin "36") (pinfunction "PR0(XTAL2,TOSC2)_36") (pintype "bidirectional"))
    )
    (net (code "26") (name "Net-(MCP1-PROG)") (class "Default")
      (node (ref "MCP1") (pin "P$5") (pinfunction "PROG_P$5") (pintype "bidirectional"))
      (node (ref "R28") (pin "2") (pinfunction "2_2") (pintype "passive"))
    )
    (net (code "27") (name "Net-(MCP1-STAT)") (class "Default")
      (node (ref "MCP1") (pin "P$1") (pinfunction "STAT_P$1") (pintype "bidirectional"))
      (node (ref "STATUS1") (pin "A") (pinfunction "A_A") (pintype "passive"))
      (node (ref "STATUS2") (pin "C") (pinfunction "C_C") (pintype "passive"))
    )
    (net (code "28") (name "Net-(MCP1-VBAT)") (class "Default")
      (node (ref "C5") (pin "2") (pinfunction "2_2") (pintype "passive"))
      (node (ref "MCP1") (pin "P$3") (pinfunction "VBAT_P$3") (pintype "bidirectional"))
      (node (ref "SJ3") (pin "1") (pinfunction "1_1") (pintype "passive"))
      (node (ref "U$5") (pin "3") (pinfunction "S_3") (pintype "bidirectional"))
      (node (ref "U$6") (pin "3") (pinfunction "S_3") (pintype "bidirectional"))
    )
    (net (code "29") (name "Net-(MCP1-VDD)") (class "Default")
      (node (ref "C4") (pin "1") (pinfunction "1_1") (pintype "passive"))
      (node (ref "JP11") (pin "2") (pinfunction "2_2") (pintype "passive"))
      (node (ref "MCP1") (pin "P$4") (pinfunction "VDD_P$4") (pintype "bidirectional"))
      (node (ref "R15") (pin "1") (pinfunction "1_1") (pintype "passive"))
      (node (ref "R3") (pin "1") (pinfunction "1_1") (pintype "passive"))
      (node (ref "U$5") (pin "1") (pinfunction "A1_1") (pintype "bidirectional"))
      (node (ref "U$5") (pin "2") (pinfunction "A2_2") (pintype "bidirectional"))
      (node (ref "U$5") (pin "4") (pinfunction "G_4") (pintype "bidirectional"))
      (node (ref "U$6") (pin "1") (pinfunction "A1_1") (pintype "bidirectional"))
      (node (ref "U$6") (pin "2") (pinfunction "A2_2") (pintype "bidirectional"))
      (node (ref "U$6") (pin "4") (pinfunction "G_4") (pintype "bidirectional"))
      (node (ref "V+_BASE") (pin "TP") (pinfunction "TP_TP") (pintype "input"))
    )
    (net (code "30") (name "Net-(MPU9150-CPOUT)") (class "Default")
      (node (ref "C18") (pin "2") (pinfunction "2_2") (pintype "passive"))
      (node (ref "MPU9150") (pin "20") (pinfunction "CPOUT_20") (pintype "bidirectional"))
    )
    (net (code "31") (name "Net-(MPU9150-REGOUT)") (class "Default")
      (node (ref "C17") (pin "2") (pinfunction "2_2") (pintype "passive"))
      (node (ref "MPU9150") (pin "10") (pinfunction "REGOUT_10") (pintype "bidirectional"))
    )
    (net (code "32") (name "Net-(PWR-PadA)") (class "Default")
      (node (ref "PWR") (pin "A") (pinfunction "A_A") (pintype "passive"))
      (node (ref "R2") (pin "1") (pinfunction "1_1") (pintype "passive"))
    )
    (net (code "33") (name "Net-(R15-Pad2)") (class "Default")
      (node (ref "R15") (pin "2") (pinfunction "2_2") (pintype "passive"))
      (node (ref "STATUS2") (pin "A") (pinfunction "A_A") (pintype "passive"))
    )
    (net (code "34") (name "Net-(R27-Pad1)") (class "Default")
      (node (ref "R27") (pin "1") (pinfunction "1_1") (pintype "passive"))
      (node (ref "STATUS1") (pin "C") (pinfunction "C_C") (pintype "passive"))
    )
    (net (code "35") (name "Net-(SJ3-Pad2)") (class "Default")
      (node (ref "SJ3") (pin "2") (pinfunction "2_2") (pintype "passive"))
      (node (ref "VBAT+") (pin "TP") (pinfunction "TP_TP") (pintype "input"))
    )
    (net (code "36") (name "Net-(T5-D)") (class "Default")
      (node (ref "L1-") (pin "TP") (pinfunction "TP_TP") (pintype "input"))
      (node (ref "LED8") (pin "C") (pinfunction "C_C") (pintype "passive"))
      (node (ref "T5") (pin "3") (pinfunction "D_3") (pintype "passive"))
    )
    (net (code "37") (name "Net-(T6-D)") (class "Default")
      (node (ref "L2-") (pin "TP") (pinfunction "TP_TP") (pintype "input"))
      (node (ref "LED7") (pin "C") (pinfunction "C_C") (pintype "passive"))
      (node (ref "T6") (pin "3") (pinfunction "D_3") (pintype "passive"))
    )
    (net (code "38") (name "Net-(T7-D)") (class "Default")
      (node (ref "L3-") (pin "TP") (pinfunction "TP_TP") (pintype "input"))
      (node (ref "LED5") (pin "C") (pinfunction "C_C") (pintype "passive"))
      (node (ref "T7") (pin "3") (pinfunction "D_3") (pintype "passive"))
    )
    (net (code "39") (name "Net-(T8-D)") (class "Default")
      (node (ref "L4-") (pin "TP") (pinfunction "TP_TP") (pintype "input"))
      (node (ref "LED6") (pin "C") (pinfunction "C_C") (pintype "passive"))
      (node (ref "T8") (pin "3") (pinfunction "D_3") (pintype "passive"))
    )
    (net (code "40") (name "Net-(U$1-A)") (class "Default")
      (node (ref "M1A") (pin "TP") (pinfunction "TP_TP") (pintype "input"))
      (node (ref "U$1") (pin "OUT_A") (pinfunction "A_OUT_A") (pintype "bidirectional"))
    )
    (net (code "41") (name "Net-(U$1-B)") (class "Default")
      (node (ref "M1B") (pin "TP") (pinfunction "TP_TP") (pintype "input"))
      (node (ref "U$1") (pin "OUT_B") (pinfunction "B_OUT_B") (pintype "bidirectional"))
    )
    (net (code "42") (name "Net-(U$1-C)") (class "Default")
      (node (ref "M1C") (pin "TP") (pinfunction "TP_TP") (pintype "input"))
      (node (ref "U$1") (pin "OUT_C") (pinfunction "C_OUT_C") (pintype "bidirectional"))
    )
    (net (code "43") (name "Net-(U$1-SIG)") (class "Default")
      (node (ref "JP14") (pin "3") (pinfunction "3_3") (pintype "passive"))
      (node (ref "U$1") (pin "IN_SIGNAL") (pinfunction "SIG_IN_SIGNAL") (pintype "bidirectional"))
    )
    (net (code "44") (name "Net-(U$2-A)") (class "Default")
      (node (ref "M2A") (pin "TP") (pinfunction "TP_TP") (pintype "input"))
      (node (ref "U$2") (pin "OUT_A") (pinfunction "A_OUT_A") (pintype "bidirectional"))
    )
    (net (code "45") (name "Net-(U$2-B)") (class "Default")
      (node (ref "M2B") (pin "TP") (pinfunction "TP_TP") (pintype "input"))
      (node (ref "U$2") (pin "OUT_B") (pinfunction "B_OUT_B") (pintype "bidirectional"))
    )
    (net (code "46") (name "Net-(U$2-C)") (class "Default")
      (node (ref "M2C") (pin "TP") (pinfunction "TP_TP") (pintype "input"))
      (node (ref "U$2") (pin "OUT_C") (pinfunction "C_OUT_C") (pintype "bidirectional"))
    )
    (net (code "47") (name "Net-(U$2-SIG)") (class "Default")
      (node (ref "JP15") (pin "3") (pinfunction "3_3") (pintype "passive"))
      (node (ref "U$2") (pin "IN_SIGNAL") (pinfunction "SIG_IN_SIGNAL") (pintype "bidirectional"))
    )
    (net (code "48") (name "Net-(U$3-A)") (class "Default")
      (node (ref "M3A") (pin "TP") (pinfunction "TP_TP") (pintype "input"))
      (node (ref "U$3") (pin "OUT_A") (pinfunction "A_OUT_A") (pintype "bidirectional"))
    )
    (net (code "49") (name "Net-(U$3-B)") (class "Default")
      (node (ref "M3B") (pin "TP") (pinfunction "TP_TP") (pintype "input"))
      (node (ref "U$3") (pin "OUT_B") (pinfunction "B_OUT_B") (pintype "bidirectional"))
    )
    (net (code "50") (name "Net-(U$3-C)") (class "Default")
      (node (ref "M3C") (pin "TP") (pinfunction "TP_TP") (pintype "input"))
      (node (ref "U$3") (pin "OUT_C") (pinfunction "C_OUT_C") (pintype "bidirectional"))
    )
    (net (code "51") (name "Net-(U$3-SIG)") (class "Default")
      (node (ref "JP16") (pin "3") (pinfunction "3_3") (pintype "passive"))
      (node (ref "U$3") (pin "IN_SIGNAL") (pinfunction "SIG_IN_SIGNAL") (pintype "bidirectional"))
    )
    (net (code "52") (name "Net-(U$4-A)") (class "Default")
      (node (ref "M4A") (pin "TP") (pinfunction "TP_TP") (pintype "input"))
      (node (ref "U$4") (pin "OUT_A") (pinfunction "A_OUT_A") (pintype "bidirectional"))
    )
    (net (code "53") (name "Net-(U$4-B)") (class "Default")
      (node (ref "M4B") (pin "TP") (pinfunction "TP_TP") (pintype "input"))
      (node (ref "U$4") (pin "OUT_B") (pinfunction "B_OUT_B") (pintype "bidirectional"))
    )
    (net (code "54") (name "Net-(U$4-C)") (class "Default")
      (node (ref "M4C") (pin "TP") (pinfunction "TP_TP") (pintype "input"))
      (node (ref "U$4") (pin "OUT_C") (pinfunction "C_OUT_C") (pintype "bidirectional"))
    )
    (net (code "55") (name "Net-(U$4-SIG)") (class "Default")
      (node (ref "JP17") (pin "3") (pinfunction "3_3") (pintype "passive"))
      (node (ref "U$4") (pin "IN_SIGNAL") (pinfunction "SIG_IN_SIGNAL") (pintype "bidirectional"))
    )
    (net (code "56") (name "Net-(U2-IO1)") (class "Default")
      (node (ref "R8") (pin "1") (pinfunction "1_1") (pintype "passive"))
      (node (ref "U2") (pin "2") (pinfunction "IO1_2") (pintype "bidirectional"))
      (node (ref "X1") (pin "D-") (pinfunction "D-_D-") (pintype "bidirectional"))
    )
    (net (code "57") (name "Net-(U2-IO2)") (class "Default")
      (node (ref "R7") (pin "1") (pinfunction "1_1") (pintype "passive"))
      (node (ref "U2") (pin "3") (pinfunction "IO2_3") (pintype "bidirectional"))
      (node (ref "X1") (pin "D+") (pinfunction "D+_D+") (pintype "bidirectional"))
    )
    (net (code "58") (name "PD0") (class "Default")
      (node (ref "MC1") (pin "20") (pinfunction "PD0(OC0A)_20") (pintype "bidirectional"))
      (node (ref "X2") (pin "2") (pinfunction "S_2") (pintype "passive"))
    )
    (net (code "59") (name "PD4") (class "Default")
      (node (ref "MC1") (pin "24") (pinfunction "PD4(OC1A,SS)_24") (pintype "bidirectional"))
      (node (ref "X2") (pin "7") (pinfunction "S_7") (pintype "passive"))
    )
    (net (code "60") (name "PD5") (class "Default")
      (node (ref "MC1") (pin "25") (pinfunction "PD5(OC1B,XCK1,MOSI)_25") (pintype "bidirectional"))
      (node (ref "X2") (pin "8") (pinfunction "S_8") (pintype "passive"))
    )
    (net (code "61") (name "PDI_CLOCK") (class "Default")
      (node (ref "JP5") (pin "5") (pinfunction "5_5") (pintype "passive"))
      (node (ref "MC1") (pin "35") (pinfunction "/RESET(PDI_CLOCK)_35") (pintype "bidirectional"))
      (node (ref "R6") (pin "2") (pinfunction "2_2") (pintype "passive"))
    )
    (net (code "62") (name "PDI_DATA") (class "Default")
      (node (ref "JP5") (pin "1") (pinfunction "1_1") (pintype "passive"))
      (node (ref "MC1") (pin "34") (pinfunction "PDI(PDI_DATA)_34") (pintype "bidirectional"))
    )
    (net (code "63") (name "PWM1") (class "Default")
      (node (ref "JP1") (pin "1") (pinfunction "1_1") (pintype "passive"))
      (node (ref "MC1") (pin "10") (pinfunction "PC0(OC0A,OC0ALS,SDA)_10") (pintype "bidirectional"))
      (node (ref "PWM1") (pin "TP") (pinfunction "TP_TP") (pintype "input"))
    )
    (net (code "64") (name "PWM2") (class "Default")
      (node (ref "3V2") (pin "TP") (pinfunction "TP_TP") (pintype "input"))
      (node (ref "JP2") (pin "1") (pinfunction "1_1") (pintype "passive"))
      (node (ref "MC1") (pin "11") (pinfunction "PC1(OC0B,OC0AHS,XCK0,SCL)_11") (pintype "bidirectional"))
    )
    (net (code "65") (name "PWM3") (class "Default")
      (node (ref "3V4") (pin "TP") (pinfunction "TP_TP") (pintype "input"))
      (node (ref "JP3") (pin "1") (pinfunction "1_1") (pintype "passive"))
      (node (ref "MC1") (pin "12") (pinfunction "PC2(OC0C,OC0BLS,RXD0)_12") (pintype "bidirectional"))
    )
    (net (code "66") (name "PWM4") (class "Default")
      (node (ref "3V5") (pin "TP") (pinfunction "TP_TP") (pintype "input"))
      (node (ref "JP4") (pin "1") (pinfunction "1_1") (pintype "passive"))
      (node (ref "MC1") (pin "13") (pinfunction "PC3(OC0D,OC0BHS,TXD0)_13") (pintype "bidirectional"))
    )
    (net (code "67") (name "PWM5") (class "Default")
      (node (ref "3V1") (pin "TP") (pinfunction "TP_TP") (pintype "input"))
      (node (ref "JP6") (pin "1") (pinfunction "1_1") (pintype "passive"))
      (node (ref "MC1") (pin "14") (pinfunction "PC4(OC0CLS,OC1A,SS)_14") (pintype "bidirectional"))
    )
    (net (code "68") (name "PWM6") (class "Default")
      (node (ref "3V6") (pin "TP") (pinfunction "TP_TP") (pintype "input"))
      (node (ref "JP7") (pin "1") (pinfunction "1_1") (pintype "passive"))
      (node (ref "MC1") (pin "15") (pinfunction "PC5(OC0CHS,OC1B,XCK1,MOSI)_15") (pintype "bidirectional"))
    )
    (net (code "69") (name "PWM7") (class "Default")
      (node (ref "3V7") (pin "TP") (pinfunction "TP_TP") (pintype "input"))
      (node (ref "JP8") (pin "1") (pinfunction "1_1") (pintype "passive"))
      (node (ref "MC1") (pin "16") (pinfunction "PC6(OC0DLS,RXD1,MISO,CLK)_16") (pintype "bidirectional"))
    )
    (net (code "70") (name "PWM8") (class "Default")
      (node (ref "3V8") (pin "TP") (pinfunction "TP_TP") (pintype "input"))
      (node (ref "JP9") (pin "1") (pinfunction "1_1") (pintype "passive"))
      (node (ref "MC1") (pin "17") (pinfunction "PC7(OC0DHS,TXD1,SCK,EVOUT,CLK)_17") (pintype "bidirectional"))
    )
    (net (code "71") (name "RXD0") (class "Default")
      (node (ref "MC1") (pin "22") (pinfunction "PD2(OC0C,RXD0)_22") (pintype "bidirectional"))
      (node (ref "X2") (pin "4") (pinfunction "S_4") (pintype "passive"))
    )
    (net (code "72") (name "RXD2") (class "Default")
      (node (ref "MC1") (pin "32") (pinfunction "PE2(OC0C,RXD0)_32") (pintype "bidirectional"))
      (node (ref "X4") (pin "2") (pinfunction "S_2") (pintype "passive"))
    )
    (net (code "73") (name "SCL") (class "Default")
      (node (ref "MC1") (pin "29") (pinfunction "PE1(OC0B,XCK0,SCL)_29") (pintype "bidirectional"))
      (node (ref "MPU9150") (pin "23") (pinfunction "SCL_23") (pintype "bidirectional"))
      (node (ref "R4") (pin "1") (pinfunction "1_1") (pintype "passive"))
    )
    (net (code "74") (name "SDA") (class "Default")
      (node (ref "MC1") (pin "28") (pinfunction "PE0(OC0A,SDA)_28") (pintype "bidirectional"))
      (node (ref "MPU9150") (pin "24") (pinfunction "SDA_24") (pintype "bidirectional"))
      (node (ref "R5") (pin "1") (pinfunction "1_1") (pintype "passive"))
    )
    (net (code "75") (name "TXD0") (class "Default")
      (node (ref "MC1") (pin "23") (pinfunction "PD3(OC0D,TXD0)_23") (pintype "bidirectional"))
      (node (ref "X2") (pin "5") (pinfunction "S_5") (pintype "passive"))
    )
    (net (code "76") (name "TXD2") (class "Default")
      (node (ref "MC1") (pin "33") (pinfunction "PE3(OC0D,TXD0)_33") (pintype "bidirectional"))
      (node (ref "X4") (pin "3") (pinfunction "S_3") (pintype "passive"))
    )
    (net (code "77") (name "USBCNTRL") (class "Default")
      (node (ref "MC1") (pin "6") (pinfunction "PB2(ADC10,DAC0)_6") (pintype "bidirectional"))
      (node (ref "R20") (pin "1") (pinfunction "1_1") (pintype "passive"))
      (node (ref "R21") (pin "2") (pinfunction "2_2") (pintype "passive"))
    )
    (net (code "78") (name "V+") (class "Default")
      (node (ref "JP10") (pin "2") (pinfunction "2_2") (pintype "passive"))
      (node (ref "R21") (pin "1") (pinfunction "1_1") (pintype "passive"))
      (node (ref "SJ2") (pin "2") (pinfunction "2_2") (pintype "passive"))
      (node (ref "U2") (pin "4") (pinfunction "VCC_4") (pintype "power_in"))
      (node (ref "V+") (pin "TP") (pinfunction "TP_TP") (pintype "input"))
      (node (ref "X1") (pin "VBUS") (pinfunction "VBUS_VBUS") (pintype "bidirectional"))
    )
    (net (code "79") (name "VCC") (class "Default")
      (node (ref "D6") (pin "2") (pinfunction "A2_2") (pintype "passive"))
      (node (ref "JP1") (pin "2") (pinfunction "2_2") (pintype "passive"))
      (node (ref "JP14") (pin "2") (pinfunction "2_2") (pintype "passive"))
      (node (ref "JP2") (pin "2") (pinfunction "2_2") (pintype "passive"))
      (node (ref "JP3") (pin "2") (pinfunction "2_2") (pintype "passive"))
      (node (ref "JP4") (pin "2") (pinfunction "2_2") (pintype "passive"))
      (node (ref "JP6") (pin "2") (pinfunction "2_2") (pintype "passive"))
      (node (ref "JP7") (pin "2") (pinfunction "2_2") (pintype "passive"))
      (node (ref "JP8") (pin "2") (pinfunction "2_2") (pintype "passive"))
      (node (ref "JP9") (pin "2") (pinfunction "2_2") (pintype "passive"))
      (node (ref "L1+") (pin "TP") (pinfunction "TP_TP") (pintype "input"))
      (node (ref "L2+") (pin "TP") (pinfunction "TP_TP") (pintype "input"))
      (node (ref "L3+") (pin "TP") (pinfunction "TP_TP") (pintype "input"))
      (node (ref "L4+") (pin "TP") (pinfunction "TP_TP") (pintype "input"))
      (node (ref "R11") (pin "2") (pinfunction "2_2") (pintype "passive"))
      (node (ref "R12") (pin "2") (pinfunction "2_2") (pintype "passive"))
      (node (ref "R13") (pin "2") (pinfunction "2_2") (pintype "passive"))
      (node (ref "R14") (pin "2") (pinfunction "2_2") (pintype "passive"))
      (node (ref "SJ3") (pin "3") (pinfunction "3_3") (pintype "passive"))
      (node (ref "U$1") (pin "IN_P") (pinfunction "+_IN_P") (pintype "bidirectional"))
      (node (ref "U$2") (pin "IN_P") (pinfunction "+_IN_P") (pintype "bidirectional"))
      (node (ref "U$3") (pin "IN_P") (pinfunction "+_IN_P") (pintype "bidirectional"))
      (node (ref "U$4") (pin "IN_P") (pinfunction "+_IN_P") (pintype "bidirectional"))
      (node (ref "U$5") (pin "5") (pinfunction "D1_5") (pintype "bidirectional"))
      (node (ref "U$5") (pin "6") (pinfunction "D2_6") (pintype "bidirectional"))
      (node (ref "U$5") (pin "7") (pinfunction "K1_7") (pintype "bidirectional"))
      (node (ref "U$5") (pin "8") (pinfunction "K2_8") (pintype "bidirectional"))
      (node (ref "U$6") (pin "5") (pinfunction "D1_5") (pintype "bidirectional"))
      (node (ref "U$6") (pin "6") (pinfunction "D2_6") (pintype "bidirectional"))
      (node (ref "U$6") (pin "7") (pinfunction "K1_7") (pintype "bidirectional"))
      (node (ref "U$6") (pin "8") (pinfunction "K2_8") (pintype "bidirectional"))
      (node (ref "X2") (pin "6") (pinfunction "S_6") (pintype "passive"))
    )
    (net (code "80") (name "XCK0") (class "Default")
      (node (ref "MC1") (pin "21") (pinfunction "PD1(OC0B,XCK0)_21") (pintype "bidirectional"))
      (node (ref "X2") (pin "3") (pinfunction "S_3") (pintype "passive"))
    )
    (net (code "81") (name "unconnected-(JP15-Pad1)") (class "Default")
      (node (ref "JP15") (pin "1") (pinfunction "1_1") (pintype "passive"))
    )
    (net (code "82") (name "unconnected-(JP15-Pad2)") (class "Default")
      (node (ref "JP15") (pin "2") (pinfunction "2_2") (pintype "passive"))
    )
    (net (code "83") (name "unconnected-(JP16-Pad1)") (class "Default")
      (node (ref "JP16") (pin "1") (pinfunction "1_1") (pintype "passive"))
    )
    (net (code "84") (name "unconnected-(JP16-Pad2)") (class "Default")
      (node (ref "JP16") (pin "2") (pinfunction "2_2") (pintype "passive"))
    )
    (net (code "85") (name "unconnected-(JP17-Pad1)") (class "Default")
      (node (ref "JP17") (pin "1") (pinfunction "1_1") (pintype "passive"))
    )
    (net (code "86") (name "unconnected-(JP17-Pad2)") (class "Default")
      (node (ref "JP17") (pin "2") (pinfunction "2_2") (pintype "passive"))
    )
    (net (code "87") (name "unconnected-(MC1-PA5(ADC5,AC5)-Pad1)") (class "Default")
      (node (ref "MC1") (pin "1") (pinfunction "PA5(ADC5,AC5)_1") (pintype "bidirectional"))
    )
    (net (code "88") (name "unconnected-(MC1-PA6(ADC6,AC6,AC1OUT)-Pad2)") (class "Default")
      (node (ref "MC1") (pin "2") (pinfunction "PA6(ADC6,AC6,AC1OUT)_2") (pintype "bidirectional"))
    )
    (net (code "89") (name "unconnected-(MC1-PB3(ADC11,DAC1)-Pad7)") (class "Default")
      (node (ref "MC1") (pin "7") (pinfunction "PB3(ADC11,DAC1)_7") (pintype "bidirectional"))
    )
    (net (code "90") (name "unconnected-(MPU9150-CLKOUT-Pad22)") (class "Default")
      (node (ref "MPU9150") (pin "22") (pinfunction "CLKOUT_22") (pintype "bidirectional"))
    )
    (net (code "91") (name "unconnected-(MPU9150-E_SCL-Pad7)") (class "Default")
      (node (ref "MPU9150") (pin "7") (pinfunction "E_SCL_7") (pintype "bidirectional"))
    )
    (net (code "92") (name "unconnected-(MPU9150-E_SDA-Pad6)") (class "Default")
      (node (ref "MPU9150") (pin "6") (pinfunction "E_SDA_6") (pintype "bidirectional"))
    )
    (net (code "93") (name "unconnected-(X6A-S-Pad1)") (class "Default")
      (node (ref "X6") (pin "1") (pinfunction "S_1") (pintype "passive"))
    )
  )
)
